# PCIe_JTAG.net
KiCad netlist of a schematic drawn in Altium Designer
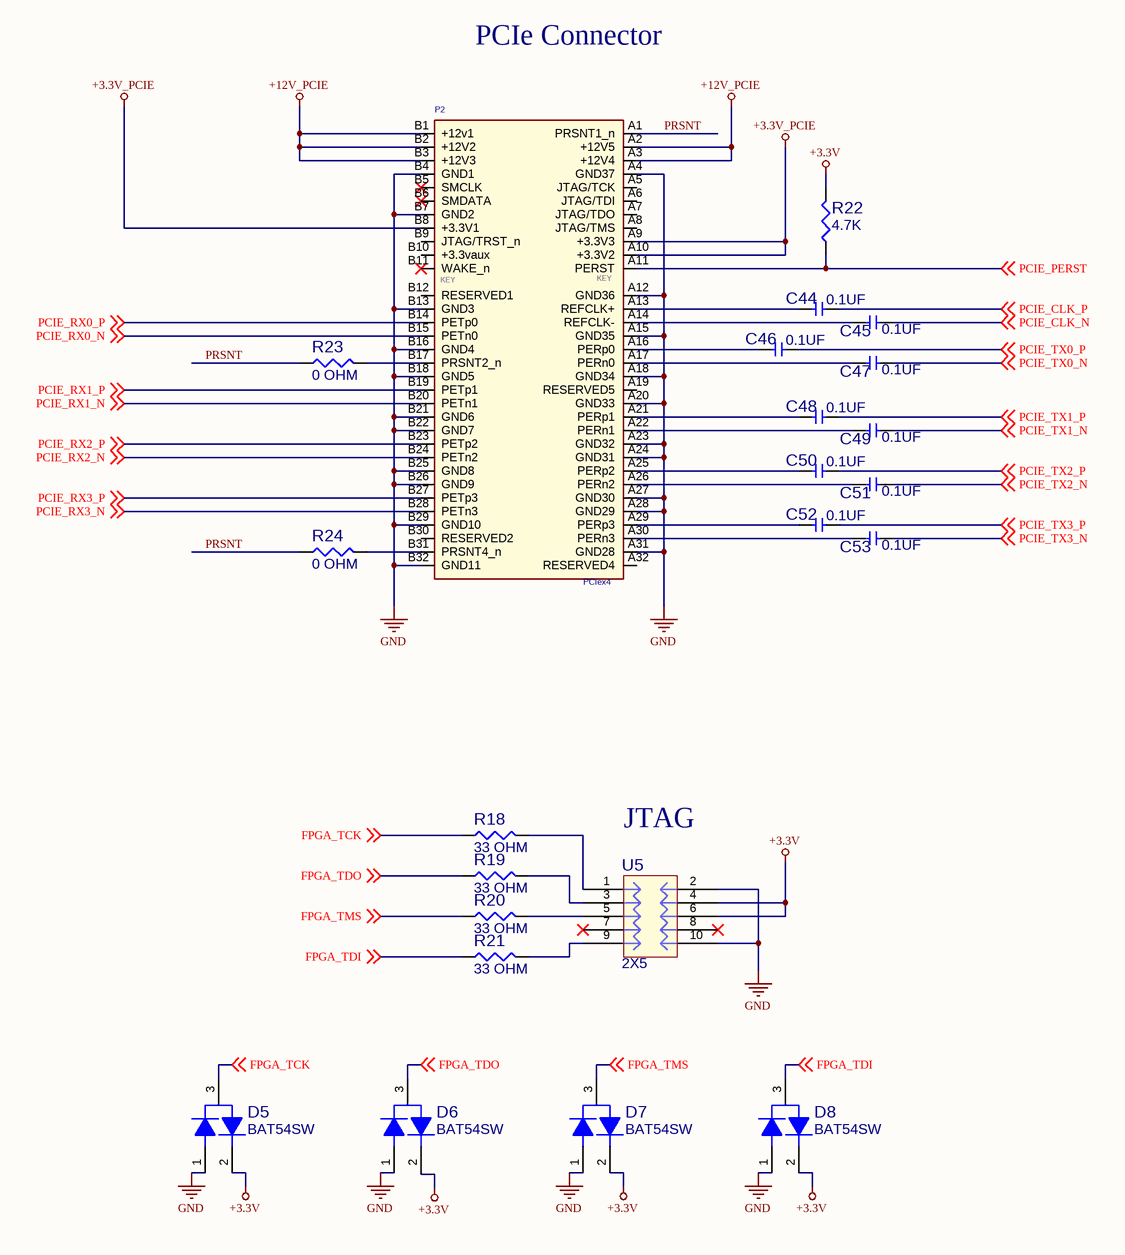
[diagram p0: PCIe_JTAG.SchDoc]

(export (version "E")
  (design (tool "Eeschema 10.0.6"))
  (components
    (comp (ref "C44")
      (value "0.1UF")
      (footprint "CAPC1005X06N")
      (description "CAP, CER, 0.1UF, 50V, 10%, X7R, AEC-Q200, 0402")
      (fields
        (field (name "MFG PART NUM") "CGA2B3X7R1H104K050BB")
        (field (name "VALENTIUM PART NUM") "<VALENTIUM>")
      )
      (libsource (lib "Capacitors") (part "CAP_0402_0.1UF_50V"))
    )
    (comp (ref "C45")
      (value "0.1UF")
      (footprint "CAPC1005X06N")
      (description "CAP, CER, 0.1UF, 50V, 10%, X7R, AEC-Q200, 0402")
      (fields
        (field (name "MFG PART NUM") "CGA2B3X7R1H104K050BB")
        (field (name "VALENTIUM PART NUM") "<VALENTIUM>")
      )
      (libsource (lib "Capacitors") (part "CAP_0402_0.1UF_50V"))
    )
    (comp (ref "C46")
      (value "0.1UF")
      (footprint "CAPC1005X06N")
      (description "CAP, CER, 0.1UF, 50V, 10%, X7R, AEC-Q200, 0402")
      (fields
        (field (name "MFG PART NUM") "CGA2B3X7R1H104K050BB")
        (field (name "VALENTIUM PART NUM") "<VALENTIUM>")
      )
      (libsource (lib "Capacitors") (part "CAP_0402_0.1UF_50V"))
    )
    (comp (ref "C47")
      (value "0.1UF")
      (footprint "CAPC1005X06N")
      (description "CAP, CER, 0.1UF, 50V, 10%, X7R, AEC-Q200, 0402")
      (fields
        (field (name "MFG PART NUM") "CGA2B3X7R1H104K050BB")
        (field (name "VALENTIUM PART NUM") "<VALENTIUM>")
      )
      (libsource (lib "Capacitors") (part "CAP_0402_0.1UF_50V"))
    )
    (comp (ref "C48")
      (value "0.1UF")
      (footprint "CAPC1005X06N")
      (description "CAP, CER, 0.1UF, 50V, 10%, X7R, AEC-Q200, 0402")
      (fields
        (field (name "MFG PART NUM") "CGA2B3X7R1H104K050BB")
        (field (name "VALENTIUM PART NUM") "<VALENTIUM>")
      )
      (libsource (lib "Capacitors") (part "CAP_0402_0.1UF_50V"))
    )
    (comp (ref "C49")
      (value "0.1UF")
      (footprint "CAPC1005X06N")
      (description "CAP, CER, 0.1UF, 50V, 10%, X7R, AEC-Q200, 0402")
      (fields
        (field (name "MFG PART NUM") "CGA2B3X7R1H104K050BB")
        (field (name "VALENTIUM PART NUM") "<VALENTIUM>")
      )
      (libsource (lib "Capacitors") (part "CAP_0402_0.1UF_50V"))
    )
    (comp (ref "C50")
      (value "0.1UF")
      (footprint "CAPC1005X06N")
      (description "CAP, CER, 0.1UF, 50V, 10%, X7R, AEC-Q200, 0402")
      (fields
        (field (name "MFG PART NUM") "CGA2B3X7R1H104K050BB")
        (field (name "VALENTIUM PART NUM") "<VALENTIUM>")
      )
      (libsource (lib "Capacitors") (part "CAP_0402_0.1UF_50V"))
    )
    (comp (ref "C51")
      (value "0.1UF")
      (footprint "CAPC1005X06N")
      (description "CAP, CER, 0.1UF, 50V, 10%, X7R, AEC-Q200, 0402")
      (fields
        (field (name "MFG PART NUM") "CGA2B3X7R1H104K050BB")
        (field (name "VALENTIUM PART NUM") "<VALENTIUM>")
      )
      (libsource (lib "Capacitors") (part "CAP_0402_0.1UF_50V"))
    )
    (comp (ref "C52")
      (value "0.1UF")
      (footprint "CAPC1005X06N")
      (description "CAP, CER, 0.1UF, 50V, 10%, X7R, AEC-Q200, 0402")
      (fields
        (field (name "MFG PART NUM") "CGA2B3X7R1H104K050BB")
        (field (name "VALENTIUM PART NUM") "<VALENTIUM>")
      )
      (libsource (lib "Capacitors") (part "CAP_0402_0.1UF_50V"))
    )
    (comp (ref "C53")
      (value "0.1UF")
      (footprint "CAPC1005X06N")
      (description "CAP, CER, 0.1UF, 50V, 10%, X7R, AEC-Q200, 0402")
      (fields
        (field (name "MFG PART NUM") "CGA2B3X7R1H104K050BB")
        (field (name "VALENTIUM PART NUM") "<VALENTIUM>")
      )
      (libsource (lib "Capacitors") (part "CAP_0402_0.1UF_50V"))
    )
    (comp (ref "D5")
      (value "BAT54SW")
      (footprint "SOT65P210X110-3N")
      (description "DIO, SCHOTTKY, BAT54S, DUAL SERIES, 30V, 200MA, SC-70")
      (fields (field (name "MFG PART NUM") "BAT54SWQ-7-F") (field (name "VALENTIUM PART NUM") "<VALENTIUM>"))
      (libsource (lib "Passives") (part "BAT54SW"))
    )
    (comp (ref "D6")
      (value "BAT54SW")
      (footprint "SOT65P210X110-3N")
      (description "DIO, SCHOTTKY, BAT54S, DUAL SERIES, 30V, 200MA, SC-70")
      (fields (field (name "MFG PART NUM") "BAT54SWQ-7-F") (field (name "VALENTIUM PART NUM") "<VALENTIUM>"))
      (libsource (lib "Passives") (part "BAT54SW"))
    )
    (comp (ref "D7")
      (value "BAT54SW")
      (footprint "SOT65P210X110-3N")
      (description "DIO, SCHOTTKY, BAT54S, DUAL SERIES, 30V, 200MA, SC-70")
      (fields (field (name "MFG PART NUM") "BAT54SWQ-7-F") (field (name "VALENTIUM PART NUM") "<VALENTIUM>"))
      (libsource (lib "Passives") (part "BAT54SW"))
    )
    (comp (ref "D8")
      (value "BAT54SW")
      (footprint "SOT65P210X110-3N")
      (description "DIO, SCHOTTKY, BAT54S, DUAL SERIES, 30V, 200MA, SC-70")
      (fields (field (name "MFG PART NUM") "BAT54SWQ-7-F") (field (name "VALENTIUM PART NUM") "<VALENTIUM>"))
      (libsource (lib "Passives") (part "BAT54SW"))
    )
    (comp (ref "P2")
      (value "PCIex4")
      (footprint "PCIE_4LANE_EDGE")
      (description "PCIE x4 Edge Connector,OrCAD Symbol,NC")
      (fields (field (name "PART NUMBER") "451") (field (name "MANUFACTURER") "NA"))
      (libsource (lib "Connectors") (part "PCIex4"))
    )
    (comp (ref "R18")
      (value "33 OHM")
      (footprint "RESC2012X50N")
      (description "RES, 33 OHM, 1%, 1/8W, TF, 0805")
      (fields
        (field (name "MFG PART NUM") "CRCW080533R0FKEA")
        (field (name "VELENTIUM PART NUM") "<VELENTIUM>")
      )
      (libsource (lib "Resistors") (part "RES_0805_33"))
    )
    (comp (ref "R19")
      (value "33 OHM")
      (footprint "RESC2012X50N")
      (description "RES, 33 OHM, 1%, 1/8W, TF, 0805")
      (fields
        (field (name "MFG PART NUM") "CRCW080533R0FKEA")
        (field (name "VELENTIUM PART NUM") "<VELENTIUM>")
      )
      (libsource (lib "Resistors") (part "RES_0805_33"))
    )
    (comp (ref "R20")
      (value "33 OHM")
      (footprint "RESC2012X50N")
      (description "RES, 33 OHM, 1%, 1/8W, TF, 0805")
      (fields
        (field (name "MFG PART NUM") "CRCW080533R0FKEA")
        (field (name "VELENTIUM PART NUM") "<VELENTIUM>")
      )
      (libsource (lib "Resistors") (part "RES_0805_33"))
    )
    (comp (ref "R21")
      (value "33 OHM")
      (footprint "RESC2012X50N")
      (description "RES, 33 OHM, 1%, 1/8W, TF, 0805")
      (fields
        (field (name "MFG PART NUM") "CRCW080533R0FKEA")
        (field (name "VELENTIUM PART NUM") "<VELENTIUM>")
      )
      (libsource (lib "Resistors") (part "RES_0805_33"))
    )
    (comp (ref "R22")
      (value "4.7K")
      (footprint "RESC1608X50N")
      (description "RES, 4.7K, 1%, 1/10W, TF, 0603")
      (fields (field (name "MFG PART NUM") "ERJ-3EKF4701V") (field (name "VELENTIUM PART NUM") "<VELENTIUM>"))
      (libsource (lib "Resistors") (part "RES_0603_4.7K"))
    )
    (comp (ref "R23")
      (value "0 OHM")
      (footprint "RESC1005X04N")
      (description "RES, 0. OHM, 1%, 1/16W, TF, AEC-Q200, 0402")
      (fields (field (name "MFG PART NUM") "ERJ-2GE0R00X") (field (name "VELENTIUM PART NUM") "<VELENTIUM>"))
      (libsource (lib "Resistors") (part "RES_0402_0"))
    )
    (comp (ref "R24")
      (value "0 OHM")
      (footprint "RESC1005X04N")
      (description "RES, 0. OHM, 1%, 1/16W, TF, AEC-Q200, 0402")
      (fields (field (name "MFG PART NUM") "ERJ-2GE0R00X") (field (name "VELENTIUM PART NUM") "<VELENTIUM>"))
      (libsource (lib "Resistors") (part "RES_0402_0"))
    )
    (comp (ref "U5")
      (value "2X5")
      (footprint "SAMTEC_HTST-105-01-L-DV-A")
      (description "CONN, HDR, 2X5, VERT, 0.1IN  SHROUDED, SMT, HTSH SERIES")
      (fields
        (field (name "MFG PART NUM") "HTST-105-01-L-DV-A")
        (field (name "VALENTIUM PART NUM") "<VALENTIUM>")
      )
      (libsource (lib "Connectors") (part "SAMTEC-HTSH-105-01-L-DV"))
    )
  )
  (nets
    (net (code "1") (name "+3.3V") (class "Default")
      (node (ref "D5") (pin "2") (pinfunction "2_2") (pintype "passive"))
      (node (ref "D6") (pin "2") (pinfunction "2_2") (pintype "passive"))
      (node (ref "D7") (pin "2") (pinfunction "2_2") (pintype "passive"))
      (node (ref "D8") (pin "2") (pinfunction "2_2") (pintype "passive"))
      (node (ref "R22") (pin "2") (pinfunction "2_2") (pintype "passive"))
      (node (ref "U5") (pin "4") (pinfunction "P4_4") (pintype "passive"))
      (node (ref "U5") (pin "6") (pinfunction "P6_6") (pintype "passive"))
    )
    (net (code "2") (name "+3.3V_PCIE") (class "Default")
      (node (ref "P2") (pin "A10") (pinfunction "+3.3V2_A10") (pintype "passive"))
      (node (ref "P2") (pin "A9") (pinfunction "+3.3V3_A9") (pintype "passive"))
      (node (ref "P2") (pin "B8") (pinfunction "+3.3V1_B8") (pintype "power_in"))
    )
    (net (code "3") (name "+12V_PCIE") (class "Default")
      (node (ref "P2") (pin "A2") (pinfunction "+12V5_A2") (pintype "passive"))
      (node (ref "P2") (pin "A3") (pinfunction "+12V4_A3") (pintype "passive"))
      (node (ref "P2") (pin "B1") (pinfunction "+12v1_B1") (pintype "power_in"))
      (node (ref "P2") (pin "B2") (pinfunction "+12V2_B2") (pintype "power_in"))
      (node (ref "P2") (pin "B3") (pinfunction "+12V3_B3") (pintype "power_in"))
    )
    (net (code "4") (name "/PRSNT") (class "Default")
      (node (ref "P2") (pin "A1") (pinfunction "PRSNT1_n_A1") (pintype "passive"))
      (node (ref "R23") (pin "1") (pinfunction "1_1") (pintype "passive"))
      (node (ref "R24") (pin "1") (pinfunction "1_1") (pintype "passive"))
    )
    (net (code "5") (name "FPGA_TCK") (class "Default")
      (node (ref "D5") (pin "3") (pinfunction "3_3") (pintype "passive"))
      (node (ref "R18") (pin "1") (pinfunction "1_1") (pintype "passive"))
    )
    (net (code "6") (name "FPGA_TDI") (class "Default")
      (node (ref "D8") (pin "3") (pinfunction "3_3") (pintype "passive"))
      (node (ref "R21") (pin "1") (pinfunction "1_1") (pintype "passive"))
    )
    (net (code "7") (name "FPGA_TDO") (class "Default")
      (node (ref "D6") (pin "3") (pinfunction "3_3") (pintype "passive"))
      (node (ref "R19") (pin "1") (pinfunction "1_1") (pintype "passive"))
    )
    (net (code "8") (name "FPGA_TMS") (class "Default")
      (node (ref "D7") (pin "3") (pinfunction "3_3") (pintype "passive"))
      (node (ref "R20") (pin "1") (pinfunction "1_1") (pintype "passive"))
    )
    (net (code "9") (name "GND") (class "Default")
      (node (ref "D5") (pin "1") (pinfunction "1_1") (pintype "passive"))
      (node (ref "D6") (pin "1") (pinfunction "1_1") (pintype "passive"))
      (node (ref "D7") (pin "1") (pinfunction "1_1") (pintype "passive"))
      (node (ref "D8") (pin "1") (pinfunction "1_1") (pintype "passive"))
      (node (ref "P2") (pin "A12") (pinfunction "GND36_A12") (pintype "power_in"))
      (node (ref "P2") (pin "A15") (pinfunction "GND35_A15") (pintype "power_in"))
      (node (ref "P2") (pin "A18") (pinfunction "GND34_A18") (pintype "power_in"))
      (node (ref "P2") (pin "A20") (pinfunction "GND33_A20") (pintype "power_in"))
      (node (ref "P2") (pin "A23") (pinfunction "GND32_A23") (pintype "power_in"))
      (node (ref "P2") (pin "A24") (pinfunction "GND31_A24") (pintype "power_in"))
      (node (ref "P2") (pin "A27") (pinfunction "GND30_A27") (pintype "power_in"))
      (node (ref "P2") (pin "A28") (pinfunction "GND29_A28") (pintype "power_in"))
      (node (ref "P2") (pin "A31") (pinfunction "GND28_A31") (pintype "power_in"))
      (node (ref "P2") (pin "A4") (pinfunction "GND37_A4") (pintype "power_in"))
      (node (ref "P2") (pin "B13") (pinfunction "GND3_B13") (pintype "power_in"))
      (node (ref "P2") (pin "B16") (pinfunction "GND4_B16") (pintype "power_in"))
      (node (ref "P2") (pin "B18") (pinfunction "GND5_B18") (pintype "power_in"))
      (node (ref "P2") (pin "B21") (pinfunction "GND6_B21") (pintype "power_in"))
      (node (ref "P2") (pin "B22") (pinfunction "GND7_B22") (pintype "power_in"))
      (node (ref "P2") (pin "B25") (pinfunction "GND8_B25") (pintype "power_in"))
      (node (ref "P2") (pin "B26") (pinfunction "GND9_B26") (pintype "power_in"))
      (node (ref "P2") (pin "B29") (pinfunction "GND10_B29") (pintype "power_in"))
      (node (ref "P2") (pin "B32") (pinfunction "GND11_B32") (pintype "power_in"))
      (node (ref "P2") (pin "B4") (pinfunction "GND1_B4") (pintype "power_in"))
      (node (ref "P2") (pin "B7") (pinfunction "GND2_B7") (pintype "power_in"))
      (node (ref "U5") (pin "10") (pinfunction "P10_10") (pintype "passive"))
      (node (ref "U5") (pin "2") (pinfunction "P2_2") (pintype "passive"))
    )
    (net (code "10") (name "Net-(P2-PERn0)") (class "Default")
      (node (ref "C47") (pin "1") (pinfunction "1_1") (pintype "passive"))
      (node (ref "P2") (pin "A17") (pinfunction "PERn0_A17") (pintype "passive"))
    )
    (net (code "11") (name "Net-(P2-PERn1)") (class "Default")
      (node (ref "C49") (pin "1") (pinfunction "1_1") (pintype "passive"))
      (node (ref "P2") (pin "A22") (pinfunction "PERn1_A22") (pintype "passive"))
    )
    (net (code "12") (name "Net-(P2-PERn2)") (class "Default")
      (node (ref "C51") (pin "1") (pinfunction "1_1") (pintype "passive"))
      (node (ref "P2") (pin "A26") (pinfunction "PERn2_A26") (pintype "passive"))
    )
    (net (code "13") (name "Net-(P2-PERn3)") (class "Default")
      (node (ref "C53") (pin "1") (pinfunction "1_1") (pintype "passive"))
      (node (ref "P2") (pin "A30") (pinfunction "PERn3_A30") (pintype "passive"))
    )
    (net (code "14") (name "Net-(P2-PERp0)") (class "Default")
      (node (ref "C46") (pin "1") (pinfunction "1_1") (pintype "passive"))
      (node (ref "P2") (pin "A16") (pinfunction "PERp0_A16") (pintype "passive"))
    )
    (net (code "15") (name "Net-(P2-PERp1)") (class "Default")
      (node (ref "C48") (pin "1") (pinfunction "1_1") (pintype "passive"))
      (node (ref "P2") (pin "A21") (pinfunction "PERp1_A21") (pintype "passive"))
    )
    (net (code "16") (name "Net-(P2-PERp2)") (class "Default")
      (node (ref "C50") (pin "1") (pinfunction "1_1") (pintype "passive"))
      (node (ref "P2") (pin "A25") (pinfunction "PERp2_A25") (pintype "passive"))
    )
    (net (code "17") (name "Net-(P2-PERp3)") (class "Default")
      (node (ref "C52") (pin "1") (pinfunction "1_1") (pintype "passive"))
      (node (ref "P2") (pin "A29") (pinfunction "PERp3_A29") (pintype "passive"))
    )
    (net (code "18") (name "Net-(P2-PRSNT2_n)") (class "Default")
      (node (ref "P2") (pin "B17") (pinfunction "PRSNT2_n_B17") (pintype "passive"))
      (node (ref "R23") (pin "2") (pinfunction "2_2") (pintype "passive"))
    )
    (net (code "19") (name "Net-(P2-PRSNT4_n)") (class "Default")
      (node (ref "P2") (pin "B31") (pinfunction "PRSNT4_n_B31") (pintype "passive"))
      (node (ref "R24") (pin "2") (pinfunction "2_2") (pintype "passive"))
    )
    (net (code "20") (name "Net-(P2-REFCLK+)") (class "Default")
      (node (ref "C44") (pin "1") (pinfunction "1_1") (pintype "passive"))
      (node (ref "P2") (pin "A13") (pinfunction "REFCLK+_A13") (pintype "passive"))
    )
    (net (code "21") (name "Net-(P2-REFCLK-)") (class "Default")
      (node (ref "C45") (pin "1") (pinfunction "1_1") (pintype "passive"))
      (node (ref "P2") (pin "A14") (pinfunction "REFCLK-_A14") (pintype "passive"))
    )
    (net (code "22") (name "Net-(U5-P1)") (class "Default")
      (node (ref "R18") (pin "2") (pinfunction "2_2") (pintype "passive"))
      (node (ref "U5") (pin "1") (pinfunction "P1_1") (pintype "passive"))
    )
    (net (code "23") (name "Net-(U5-P3)") (class "Default")
      (node (ref "R19") (pin "2") (pinfunction "2_2") (pintype "passive"))
      (node (ref "U5") (pin "3") (pinfunction "P3_3") (pintype "passive"))
    )
    (net (code "24") (name "Net-(U5-P5)") (class "Default")
      (node (ref "R20") (pin "2") (pinfunction "2_2") (pintype "passive"))
      (node (ref "U5") (pin "5") (pinfunction "P5_5") (pintype "passive"))
    )
    (net (code "25") (name "Net-(U5-P9)") (class "Default")
      (node (ref "R21") (pin "2") (pinfunction "2_2") (pintype "passive"))
      (node (ref "U5") (pin "9") (pinfunction "P9_9") (pintype "passive"))
    )
    (net (code "26") (name "PCIE_CLK_N") (class "Default")
      (node (ref "C45") (pin "2") (pinfunction "2_2") (pintype "passive"))
    )
    (net (code "27") (name "PCIE_CLK_P") (class "Default")
      (node (ref "C44") (pin "2") (pinfunction "2_2") (pintype "passive"))
    )
    (net (code "28") (name "PCIE_PERST") (class "Default")
      (node (ref "P2") (pin "A11") (pinfunction "PERST_A11") (pintype "passive"))
      (node (ref "R22") (pin "1") (pinfunction "1_1") (pintype "passive"))
    )
    (net (code "29") (name "PCIE_RX0_N") (class "Default")
      (node (ref "P2") (pin "B15") (pinfunction "PETn0_B15") (pintype "passive"))
    )
    (net (code "30") (name "PCIE_RX0_P") (class "Default")
      (node (ref "P2") (pin "B14") (pinfunction "PETp0_B14") (pintype "passive"))
    )
    (net (code "31") (name "PCIE_RX1_N") (class "Default")
      (node (ref "P2") (pin "B20") (pinfunction "PETn1_B20") (pintype "passive"))
    )
    (net (code "32") (name "PCIE_RX1_P") (class "Default")
      (node (ref "P2") (pin "B19") (pinfunction "PETp1_B19") (pintype "passive"))
    )
    (net (code "33") (name "PCIE_RX2_N") (class "Default")
      (node (ref "P2") (pin "B24") (pinfunction "PETn2_B24") (pintype "passive"))
    )
    (net (code "34") (name "PCIE_RX2_P") (class "Default")
      (node (ref "P2") (pin "B23") (pinfunction "PETp2_B23") (pintype "passive"))
    )
    (net (code "35") (name "PCIE_RX3_N") (class "Default")
      (node (ref "P2") (pin "B28") (pinfunction "PETn3_B28") (pintype "passive"))
    )
    (net (code "36") (name "PCIE_RX3_P") (class "Default")
      (node (ref "P2") (pin "B27") (pinfunction "PETp3_B27") (pintype "passive"))
    )
    (net (code "37") (name "PCIE_TX0_N") (class "Default")
      (node (ref "C47") (pin "2") (pinfunction "2_2") (pintype "passive"))
    )
    (net (code "38") (name "PCIE_TX0_P") (class "Default")
      (node (ref "C46") (pin "2") (pinfunction "2_2") (pintype "passive"))
    )
    (net (code "39") (name "PCIE_TX1_N") (class "Default")
      (node (ref "C49") (pin "2") (pinfunction "2_2") (pintype "passive"))
    )
    (net (code "40") (name "PCIE_TX1_P") (class "Default")
      (node (ref "C48") (pin "2") (pinfunction "2_2") (pintype "passive"))
    )
    (net (code "41") (name "PCIE_TX2_N") (class "Default")
      (node (ref "C51") (pin "2") (pinfunction "2_2") (pintype "passive"))
    )
    (net (code "42") (name "PCIE_TX2_P") (class "Default")
      (node (ref "C50") (pin "2") (pinfunction "2_2") (pintype "passive"))
    )
    (net (code "43") (name "PCIE_TX3_N") (class "Default")
      (node (ref "C53") (pin "2") (pinfunction "2_2") (pintype "passive"))
    )
    (net (code "44") (name "PCIE_TX3_P") (class "Default")
      (node (ref "C52") (pin "2") (pinfunction "2_2") (pintype "passive"))
    )
    (net (code "45") (name "unconnected-(P2-+3.3vaux-PadB10)") (class "Default")
      (node (ref "P2") (pin "B10") (pinfunction "+3.3vaux_B10") (pintype "passive"))
    )
    (net (code "46") (name "unconnected-(P2-JTAG{slash}TCK-PadA5)") (class "Default")
      (node (ref "P2") (pin "A5") (pinfunction "JTAG/TCK_A5") (pintype "passive"))
    )
    (net (code "47") (name "unconnected-(P2-JTAG{slash}TDI-PadA6)") (class "Default")
      (node (ref "P2") (pin "A6") (pinfunction "JTAG/TDI_A6") (pintype "passive"))
    )
    (net (code "48") (name "unconnected-(P2-JTAG{slash}TDO-PadA7)") (class "Default")
      (node (ref "P2") (pin "A7") (pinfunction "JTAG/TDO_A7") (pintype "passive"))
    )
    (net (code "49") (name "unconnected-(P2-JTAG{slash}TMS-PadA8)") (class "Default")
      (node (ref "P2") (pin "A8") (pinfunction "JTAG/TMS_A8") (pintype "passive"))
    )
    (net (code "50") (name "unconnected-(P2-JTAG{slash}TRST_n-PadB9)") (class "Default")
      (node (ref "P2") (pin "B9") (pinfunction "JTAG/TRST_n_B9") (pintype "passive"))
    )
    (net (code "51") (name "unconnected-(P2-RESERVED1-PadB12)") (class "Default")
      (node (ref "P2") (pin "B12") (pinfunction "RESERVED1_B12") (pintype "passive"))
    )
    (net (code "52") (name "unconnected-(P2-RESERVED2-PadB30)") (class "Default")
      (node (ref "P2") (pin "B30") (pinfunction "RESERVED2_B30") (pintype "passive"))
    )
    (net (code "53") (name "unconnected-(P2-RESERVED4-PadA32)") (class "Default")
      (node (ref "P2") (pin "A32") (pinfunction "RESERVED4_A32") (pintype "passive"))
    )
    (net (code "54") (name "unconnected-(P2-RESERVED5-PadA19)") (class "Default")
      (node (ref "P2") (pin "A19") (pinfunction "RESERVED5_A19") (pintype "passive"))
    )
    (net (code "55") (name "unconnected-(P2-SMCLK-PadB5)") (class "Default")
      (node (ref "P2") (pin "B5") (pinfunction "SMCLK_B5") (pintype "passive+no_connect"))
    )
    (net (code "56") (name "unconnected-(P2-SMDATA-PadB6)") (class "Default")
      (node (ref "P2") (pin "B6") (pinfunction "SMDATA_B6") (pintype "passive+no_connect"))
    )
    (net (code "57") (name "unconnected-(P2-WAKE_n-PadB11)") (class "Default")
      (node (ref "P2") (pin "B11") (pinfunction "WAKE_n_B11") (pintype "passive+no_connect"))
    )
    (net (code "58") (name "unconnected-(U5-P7-Pad7)") (class "Default")
      (node (ref "U5") (pin "7") (pinfunction "P7_7") (pintype "passive+no_connect"))
    )
    (net (code "59") (name "unconnected-(U5-P8-Pad8)") (class "Default")
      (node (ref "U5") (pin "8") (pinfunction "P8_8") (pintype "passive+no_connect"))
    )
  )
)
